# Swarm_Mini_Fet_Shield-v_01.net
KiCad netlist of a schematic drawn in EAGLE
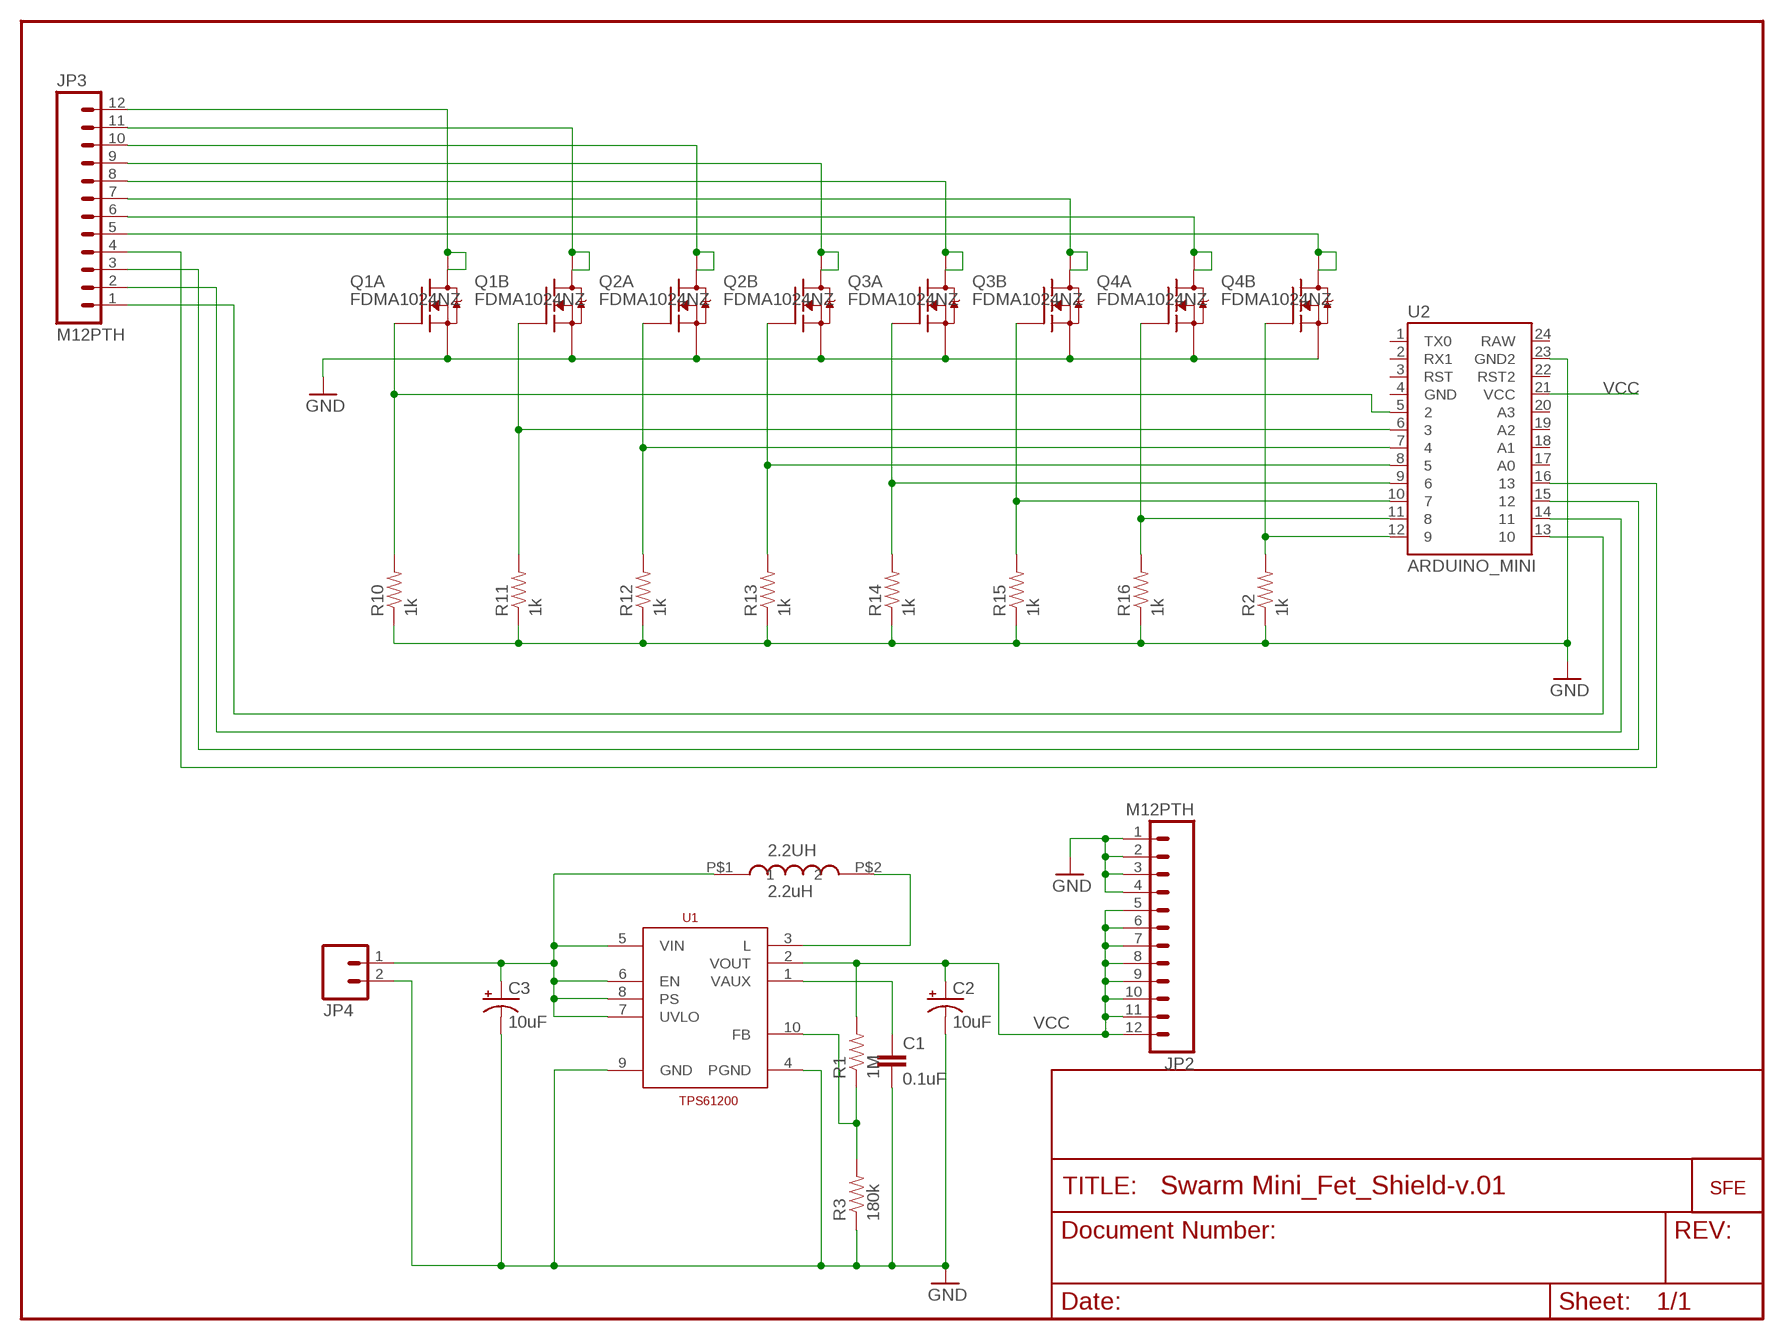
[diagram p0: schematic, sheet 1]

(export (version "E")
  (design (tool "Eeschema 10.0.6"))
  (components
    (comp (ref "2.2UH")
      (value "2.2uH")
      (footprint "eagle-import:VLF4012A")
      (libsource (lib "eagle-import") (part "VLF4012A"))
    )
    (comp (ref "C1")
      (value "0.1uF")
      (footprint "eagle-import:0805")
      (libsource (lib "eagle-import") (part "CAP0805"))
    )
    (comp (ref "C2")
      (value "10uF")
      (footprint "eagle-import:EIA3216")
      (libsource (lib "eagle-import") (part "CAP_POL1206"))
    )
    (comp (ref "C3")
      (value "10uF")
      (footprint "eagle-import:EIA3216")
      (libsource (lib "eagle-import") (part "CAP_POL1206"))
    )
    (comp (ref "JP2")
      (value "M12PTH")
      (footprint "eagle-import:1X12")
      (libsource (lib "eagle-import") (part "M12PTH"))
    )
    (comp (ref "JP3")
      (value "M12PTH")
      (footprint "eagle-import:1X12")
      (libsource (lib "eagle-import") (part "M12PTH"))
    )
    (comp (ref "JP4")
      (value "M02PTH")
      (footprint "eagle-import:1X02")
      (libsource (lib "eagle-import") (part "M02PTH"))
    )
    (comp (ref "JP5")
      (value "LOGO-SFESK")
      (footprint "eagle-import:SFE-LOGO-FLAME")
      (libsource (lib "eagle-import") (part "LOGO-SFESK"))
    )
    (comp (ref "Q1")
      (value "FDMA1024NZ")
      (footprint "eagle-import:MICROFET_2X2")
      (libsource (lib "eagle-import") (part "FDMA1024NZ"))
    )
    (comp (ref "Q2")
      (value "FDMA1024NZ")
      (footprint "eagle-import:MICROFET_2X2")
      (libsource (lib "eagle-import") (part "FDMA1024NZ"))
    )
    (comp (ref "Q3")
      (value "FDMA1024NZ")
      (footprint "eagle-import:MICROFET_2X2")
      (libsource (lib "eagle-import") (part "FDMA1024NZ"))
    )
    (comp (ref "Q4")
      (value "FDMA1024NZ")
      (footprint "eagle-import:MICROFET_2X2")
      (libsource (lib "eagle-import") (part "FDMA1024NZ"))
    )
    (comp (ref "R1")
      (value "1M")
      (footprint "eagle-import:0805")
      (libsource (lib "eagle-import") (part "RESISTOR0805-RES"))
    )
    (comp (ref "R2")
      (value "1k")
      (footprint "eagle-import:0805")
      (libsource (lib "eagle-import") (part "RESISTOR0805-RES"))
    )
    (comp (ref "R3")
      (value "180k")
      (footprint "eagle-import:0402-RES")
      (libsource (lib "eagle-import") (part "RESISTOR0402-RES"))
    )
    (comp (ref "R10")
      (value "1k")
      (footprint "eagle-import:0805")
      (libsource (lib "eagle-import") (part "RESISTOR0805-RES"))
    )
    (comp (ref "R11")
      (value "1k")
      (footprint "eagle-import:0805")
      (libsource (lib "eagle-import") (part "RESISTOR0805-RES"))
    )
    (comp (ref "R12")
      (value "1k")
      (footprint "eagle-import:0805")
      (libsource (lib "eagle-import") (part "RESISTOR0805-RES"))
    )
    (comp (ref "R13")
      (value "1k")
      (footprint "eagle-import:0805")
      (libsource (lib "eagle-import") (part "RESISTOR0805-RES"))
    )
    (comp (ref "R14")
      (value "1k")
      (footprint "eagle-import:0805")
      (libsource (lib "eagle-import") (part "RESISTOR0805-RES"))
    )
    (comp (ref "R15")
      (value "1k")
      (footprint "eagle-import:0805")
      (libsource (lib "eagle-import") (part "RESISTOR0805-RES"))
    )
    (comp (ref "R16")
      (value "1k")
      (footprint "eagle-import:0805")
      (libsource (lib "eagle-import") (part "RESISTOR0805-RES"))
    )
    (comp (ref "U1")
      (value "TPS61200")
      (footprint "eagle-import:DRC-S-PVSON-N10")
      (libsource (lib "eagle-import") (part "TPS61200"))
    )
    (comp (ref "U2")
      (value "ARDUINO_MINI")
      (footprint "eagle-import:ARDUINO_MINI")
      (libsource (lib "eagle-import") (part "ARDUINO_MINI"))
    )
  )
  (nets
    (net (code "1") (name "/VCC") (class "Default")
      (node (ref "C2") (pin "A") (pinfunction "+_A") (pintype "passive"))
      (node (ref "JP2") (pin "10") (pinfunction "10_10") (pintype "passive"))
      (node (ref "JP2") (pin "11") (pinfunction "11_11") (pintype "passive"))
      (node (ref "JP2") (pin "12") (pinfunction "12_12") (pintype "passive"))
      (node (ref "JP2") (pin "5") (pinfunction "5_5") (pintype "passive"))
      (node (ref "JP2") (pin "6") (pinfunction "6_6") (pintype "passive"))
      (node (ref "JP2") (pin "7") (pinfunction "7_7") (pintype "passive"))
      (node (ref "JP2") (pin "8") (pinfunction "8_8") (pintype "passive"))
      (node (ref "JP2") (pin "9") (pinfunction "9_9") (pintype "passive"))
      (node (ref "R1") (pin "2") (pinfunction "2_2") (pintype "passive"))
      (node (ref "U1") (pin "2") (pinfunction "VOUT_2") (pintype "bidirectional"))
      (node (ref "U2") (pin "21") (pinfunction "VCC_21") (pintype "bidirectional"))
    )
    (net (code "2") (name "GND") (class "Default")
      (node (ref "C1") (pin "2") (pinfunction "2_2") (pintype "passive"))
      (node (ref "C2") (pin "C") (pinfunction "-_C") (pintype "passive"))
      (node (ref "C3") (pin "C") (pinfunction "-_C") (pintype "passive"))
      (node (ref "JP2") (pin "1") (pinfunction "1_1") (pintype "passive"))
      (node (ref "JP2") (pin "2") (pinfunction "2_2") (pintype "passive"))
      (node (ref "JP2") (pin "3") (pinfunction "3_3") (pintype "passive"))
      (node (ref "JP2") (pin "4") (pinfunction "4_4") (pintype "passive"))
      (node (ref "JP4") (pin "2") (pinfunction "2_2") (pintype "passive"))
      (node (ref "Q1") (pin "S1") (pinfunction "S_S1") (pintype "passive"))
      (node (ref "Q1") (pin "S2") (pinfunction "S_S2") (pintype "passive"))
      (node (ref "Q2") (pin "S1") (pinfunction "S_S1") (pintype "passive"))
      (node (ref "Q2") (pin "S2") (pinfunction "S_S2") (pintype "passive"))
      (node (ref "Q3") (pin "S1") (pinfunction "S_S1") (pintype "passive"))
      (node (ref "Q3") (pin "S2") (pinfunction "S_S2") (pintype "passive"))
      (node (ref "Q4") (pin "S1") (pinfunction "S_S1") (pintype "passive"))
      (node (ref "Q4") (pin "S2") (pinfunction "S_S2") (pintype "passive"))
      (node (ref "R10") (pin "1") (pinfunction "1_1") (pintype "passive"))
      (node (ref "R11") (pin "1") (pinfunction "1_1") (pintype "passive"))
      (node (ref "R12") (pin "1") (pinfunction "1_1") (pintype "passive"))
      (node (ref "R13") (pin "1") (pinfunction "1_1") (pintype "passive"))
      (node (ref "R14") (pin "1") (pinfunction "1_1") (pintype "passive"))
      (node (ref "R15") (pin "1") (pinfunction "1_1") (pintype "passive"))
      (node (ref "R16") (pin "1") (pinfunction "1_1") (pintype "passive"))
      (node (ref "R2") (pin "1") (pinfunction "1_1") (pintype "passive"))
      (node (ref "R3") (pin "1") (pinfunction "1_1") (pintype "passive"))
      (node (ref "U1") (pin "4") (pinfunction "PGND_4") (pintype "bidirectional"))
      (node (ref "U1") (pin "9") (pinfunction "GND_9") (pintype "bidirectional"))
      (node (ref "U2") (pin "23") (pinfunction "GND2_23") (pintype "bidirectional"))
    )
    (net (code "3") (name "Net-(2.2UH-1)") (class "Default")
      (node (ref "2.2UH") (pin "P$1") (pinfunction "1_P$1") (pintype "bidirectional"))
      (node (ref "C3") (pin "A") (pinfunction "+_A") (pintype "passive"))
      (node (ref "JP4") (pin "1") (pinfunction "1_1") (pintype "passive"))
      (node (ref "U1") (pin "5") (pinfunction "VIN_5") (pintype "bidirectional"))
      (node (ref "U1") (pin "6") (pinfunction "EN_6") (pintype "bidirectional"))
      (node (ref "U1") (pin "7") (pinfunction "UVLO_7") (pintype "bidirectional"))
      (node (ref "U1") (pin "8") (pinfunction "PS_8") (pintype "bidirectional"))
    )
    (net (code "4") (name "Net-(2.2UH-2)") (class "Default")
      (node (ref "2.2UH") (pin "P$2") (pinfunction "2_P$2") (pintype "bidirectional"))
      (node (ref "U1") (pin "3") (pinfunction "L_3") (pintype "bidirectional"))
    )
    (net (code "5") (name "Net-(Q1A-D)") (class "Default")
      (node (ref "JP3") (pin "12") (pinfunction "12_12") (pintype "passive"))
      (node (ref "Q1") (pin "D1") (pinfunction "D_D1") (pintype "passive"))
      (node (ref "Q1") (pin "D1_2") (pinfunction "D1_D1_2") (pintype "passive"))
    )
    (net (code "6") (name "Net-(Q1A-G)") (class "Default")
      (node (ref "Q1") (pin "G1") (pinfunction "G_G1") (pintype "passive"))
      (node (ref "R10") (pin "2") (pinfunction "2_2") (pintype "passive"))
      (node (ref "U2") (pin "5") (pinfunction "2_5") (pintype "bidirectional"))
    )
    (net (code "7") (name "Net-(Q1B-D)") (class "Default")
      (node (ref "JP3") (pin "11") (pinfunction "11_11") (pintype "passive"))
      (node (ref "Q1") (pin "D2") (pinfunction "D_D2") (pintype "passive"))
      (node (ref "Q1") (pin "D2_2") (pinfunction "D1_D2_2") (pintype "passive"))
    )
    (net (code "8") (name "Net-(Q1B-G)") (class "Default")
      (node (ref "Q1") (pin "G2") (pinfunction "G_G2") (pintype "passive"))
      (node (ref "R11") (pin "2") (pinfunction "2_2") (pintype "passive"))
      (node (ref "U2") (pin "6") (pinfunction "3_6") (pintype "bidirectional"))
    )
    (net (code "9") (name "Net-(Q2A-D)") (class "Default")
      (node (ref "JP3") (pin "10") (pinfunction "10_10") (pintype "passive"))
      (node (ref "Q2") (pin "D1") (pinfunction "D_D1") (pintype "passive"))
      (node (ref "Q2") (pin "D1_2") (pinfunction "D1_D1_2") (pintype "passive"))
    )
    (net (code "10") (name "Net-(Q2A-G)") (class "Default")
      (node (ref "Q2") (pin "G1") (pinfunction "G_G1") (pintype "passive"))
      (node (ref "R12") (pin "2") (pinfunction "2_2") (pintype "passive"))
      (node (ref "U2") (pin "7") (pinfunction "4_7") (pintype "bidirectional"))
    )
    (net (code "11") (name "Net-(Q2B-D)") (class "Default")
      (node (ref "JP3") (pin "9") (pinfunction "9_9") (pintype "passive"))
      (node (ref "Q2") (pin "D2") (pinfunction "D_D2") (pintype "passive"))
      (node (ref "Q2") (pin "D2_2") (pinfunction "D1_D2_2") (pintype "passive"))
    )
    (net (code "12") (name "Net-(Q2B-G)") (class "Default")
      (node (ref "Q2") (pin "G2") (pinfunction "G_G2") (pintype "passive"))
      (node (ref "R13") (pin "2") (pinfunction "2_2") (pintype "passive"))
      (node (ref "U2") (pin "8") (pinfunction "5_8") (pintype "bidirectional"))
    )
    (net (code "13") (name "Net-(Q3A-D)") (class "Default")
      (node (ref "JP3") (pin "8") (pinfunction "8_8") (pintype "passive"))
      (node (ref "Q3") (pin "D1") (pinfunction "D_D1") (pintype "passive"))
      (node (ref "Q3") (pin "D1_2") (pinfunction "D1_D1_2") (pintype "passive"))
    )
    (net (code "14") (name "Net-(Q3A-G)") (class "Default")
      (node (ref "Q3") (pin "G1") (pinfunction "G_G1") (pintype "passive"))
      (node (ref "R14") (pin "2") (pinfunction "2_2") (pintype "passive"))
      (node (ref "U2") (pin "9") (pinfunction "6_9") (pintype "bidirectional"))
    )
    (net (code "15") (name "Net-(Q3B-D)") (class "Default")
      (node (ref "JP3") (pin "7") (pinfunction "7_7") (pintype "passive"))
      (node (ref "Q3") (pin "D2") (pinfunction "D_D2") (pintype "passive"))
      (node (ref "Q3") (pin "D2_2") (pinfunction "D1_D2_2") (pintype "passive"))
    )
    (net (code "16") (name "Net-(Q3B-G)") (class "Default")
      (node (ref "Q3") (pin "G2") (pinfunction "G_G2") (pintype "passive"))
      (node (ref "R15") (pin "2") (pinfunction "2_2") (pintype "passive"))
      (node (ref "U2") (pin "10") (pinfunction "7_10") (pintype "bidirectional"))
    )
    (net (code "17") (name "Net-(Q4A-D)") (class "Default")
      (node (ref "JP3") (pin "6") (pinfunction "6_6") (pintype "passive"))
      (node (ref "Q4") (pin "D1") (pinfunction "D_D1") (pintype "passive"))
      (node (ref "Q4") (pin "D1_2") (pinfunction "D1_D1_2") (pintype "passive"))
    )
    (net (code "18") (name "Net-(Q4A-G)") (class "Default")
      (node (ref "Q4") (pin "G1") (pinfunction "G_G1") (pintype "passive"))
      (node (ref "R16") (pin "2") (pinfunction "2_2") (pintype "passive"))
      (node (ref "U2") (pin "11") (pinfunction "8_11") (pintype "bidirectional"))
    )
    (net (code "19") (name "Net-(Q4B-D)") (class "Default")
      (node (ref "JP3") (pin "5") (pinfunction "5_5") (pintype "passive"))
      (node (ref "Q4") (pin "D2") (pinfunction "D_D2") (pintype "passive"))
      (node (ref "Q4") (pin "D2_2") (pinfunction "D1_D2_2") (pintype "passive"))
    )
    (net (code "20") (name "Net-(Q4B-G)") (class "Default")
      (node (ref "Q4") (pin "G2") (pinfunction "G_G2") (pintype "passive"))
      (node (ref "R2") (pin "2") (pinfunction "2_2") (pintype "passive"))
      (node (ref "U2") (pin "12") (pinfunction "9_12") (pintype "bidirectional"))
    )
    (net (code "21") (name "Net-(U1-FB)") (class "Default")
      (node (ref "R1") (pin "1") (pinfunction "1_1") (pintype "passive"))
      (node (ref "R3") (pin "2") (pinfunction "2_2") (pintype "passive"))
      (node (ref "U1") (pin "10") (pinfunction "FB_10") (pintype "bidirectional"))
    )
    (net (code "22") (name "Net-(U1-VAUX)") (class "Default")
      (node (ref "C1") (pin "1") (pinfunction "1_1") (pintype "passive"))
      (node (ref "U1") (pin "1") (pinfunction "VAUX_1") (pintype "bidirectional"))
    )
    (net (code "23") (name "Net-(U2-10)") (class "Default")
      (node (ref "JP3") (pin "1") (pinfunction "1_1") (pintype "passive"))
      (node (ref "U2") (pin "13") (pinfunction "10_13") (pintype "bidirectional"))
    )
    (net (code "24") (name "Net-(U2-11)") (class "Default")
      (node (ref "JP3") (pin "2") (pinfunction "2_2") (pintype "passive"))
      (node (ref "U2") (pin "14") (pinfunction "11_14") (pintype "bidirectional"))
    )
    (net (code "25") (name "Net-(U2-12)") (class "Default")
      (node (ref "JP3") (pin "3") (pinfunction "3_3") (pintype "passive"))
      (node (ref "U2") (pin "15") (pinfunction "12_15") (pintype "bidirectional"))
    )
    (net (code "26") (name "Net-(U2-13)") (class "Default")
      (node (ref "JP3") (pin "4") (pinfunction "4_4") (pintype "passive"))
      (node (ref "U2") (pin "16") (pinfunction "13_16") (pintype "bidirectional"))
    )
    (net (code "27") (name "unconnected-(U2-A0-Pad17)") (class "Default")
      (node (ref "U2") (pin "17") (pinfunction "A0_17") (pintype "bidirectional"))
    )
    (net (code "28") (name "unconnected-(U2-A1-Pad18)") (class "Default")
      (node (ref "U2") (pin "18") (pinfunction "A1_18") (pintype "bidirectional"))
    )
    (net (code "29") (name "unconnected-(U2-A2-Pad19)") (class "Default")
      (node (ref "U2") (pin "19") (pinfunction "A2_19") (pintype "bidirectional"))
    )
    (net (code "30") (name "unconnected-(U2-A3-Pad20)") (class "Default")
      (node (ref "U2") (pin "20") (pinfunction "A3_20") (pintype "bidirectional"))
    )
    (net (code "31") (name "unconnected-(U2-GND-Pad4)") (class "Default")
      (node (ref "U2") (pin "4") (pinfunction "GND_4") (pintype "bidirectional"))
    )
    (net (code "32") (name "unconnected-(U2-RAW-Pad24)") (class "Default")
      (node (ref "U2") (pin "24") (pinfunction "RAW_24") (pintype "bidirectional"))
    )
    (net (code "33") (name "unconnected-(U2-RST-Pad3)") (class "Default")
      (node (ref "U2") (pin "3") (pinfunction "RST_3") (pintype "bidirectional"))
    )
    (net (code "34") (name "unconnected-(U2-RST2-Pad22)") (class "Default")
      (node (ref "U2") (pin "22") (pinfunction "RST2_22") (pintype "bidirectional"))
    )
    (net (code "35") (name "unconnected-(U2-RX1-Pad2)") (class "Default")
      (node (ref "U2") (pin "2") (pinfunction "RX1_2") (pintype "bidirectional"))
    )
    (net (code "36") (name "unconnected-(U2-TX0-Pad1)") (class "Default")
      (node (ref "U2") (pin "1") (pinfunction "TX0_1") (pintype "bidirectional"))
    )
  )
)
